# schematic.net
KiCad netlist of a schematic drawn in Altium Designer
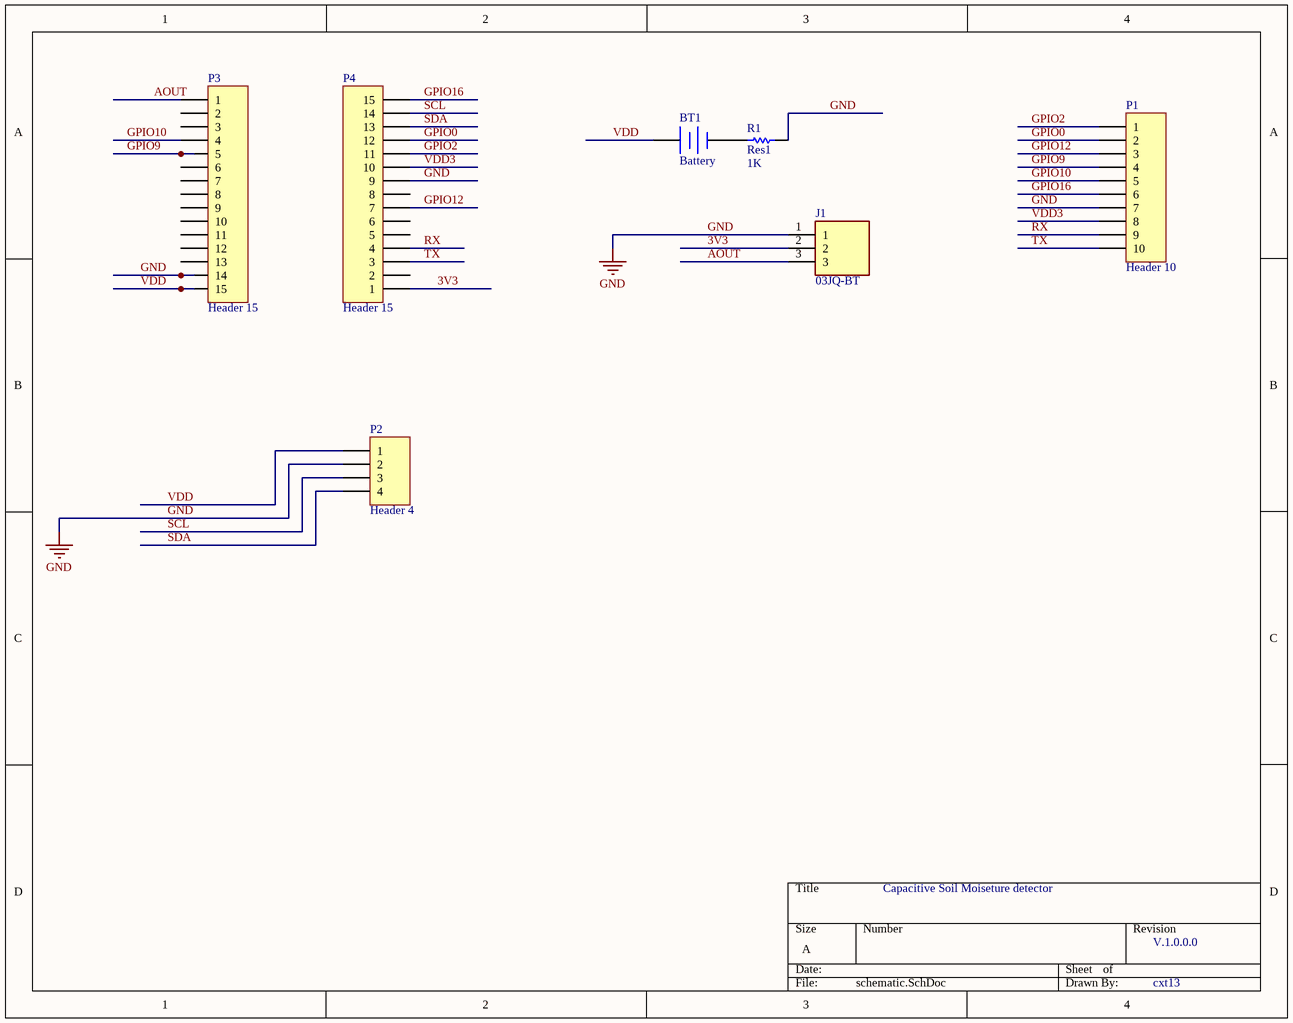
[diagram p0: schematic.SchDoc]

(export (version "E")
  (design (tool "Eeschema 10.0.6"))
  (components
    (comp (ref "BT1")
      (value "Battery")
      (footprint "BAT-2")
      (description "Multicell Battery")
      (fields (field (name "PUBLISHER") "Altium Limited"))
      (libsource (lib "Miscellaneous Devices") (part "Battery"))
    )
    (comp (ref "J1")
      (value "03JQ-BT")
      (footprint "SamacSys:SHDR3W80P0X250_1X3_1000X600X950P")
      (description "Connector")
      (libsource (lib "*") (part "03JQ-BT"))
    )
    (comp (ref "P1")
      (value "Header 10")
      (footprint "HDR1X10")
      (description "Header, 10-Pin")
      (fields (field (name "PUBLISHER") "Altium Limited"))
      (libsource (lib "Miscellaneous Connectors") (part "Header 10"))
    )
    (comp (ref "P2")
      (value "Header 4")
      (footprint "HDR1X4")
      (description "Header, 4-Pin")
      (fields (field (name "PUBLISHER") "Altium Limited"))
      (libsource (lib "Miscellaneous Connectors") (part "Header 4"))
    )
    (comp (ref "P3")
      (value "Header 15")
      (footprint "HDR1X15")
      (description "Header, 15-Pin")
      (fields (field (name "PUBLISHER") "Altium Limited"))
      (libsource (lib "") (part "Header 15_1"))
    )
    (comp (ref "P4")
      (value "Header 15")
      (footprint "HDR1X15")
      (description "Header, 15-Pin")
      (fields (field (name "PUBLISHER") "Altium Limited"))
      (libsource (lib "Miscellaneous Connectors") (part "Header 15"))
    )
    (comp (ref "R1")
      (value "Res1")
      (footprint "AXIAL-0.3")
      (description "Resistor")
      (fields (field (name "ALTIUM_VALUE") "1K") (field (name "PUBLISHER") "Altium Limited"))
      (libsource (lib "Miscellaneous Devices") (part "Res1"))
    )
  )
  (nets
    (net (code "1") (name "/3V3") (class "Default")
      (node (ref "J1") (pin "2") (pinfunction "2_2") (pintype "passive"))
      (node (ref "P4") (pin "1") (pinfunction "1_1") (pintype "passive"))
    )
    (net (code "2") (name "/AOUT") (class "Default")
      (node (ref "J1") (pin "3") (pinfunction "3_3") (pintype "passive"))
      (node (ref "P3") (pin "1") (pinfunction "1_1") (pintype "passive"))
    )
    (net (code "3") (name "/GPIO0") (class "Default")
      (node (ref "P1") (pin "2") (pinfunction "2_2") (pintype "passive"))
      (node (ref "P4") (pin "12") (pinfunction "12_12") (pintype "passive"))
    )
    (net (code "4") (name "/GPIO2") (class "Default")
      (node (ref "P1") (pin "1") (pinfunction "1_1") (pintype "passive"))
      (node (ref "P4") (pin "11") (pinfunction "11_11") (pintype "passive"))
    )
    (net (code "5") (name "/GPIO9") (class "Default")
      (node (ref "P1") (pin "4") (pinfunction "4_4") (pintype "passive"))
      (node (ref "P3") (pin "5") (pinfunction "5_5") (pintype "passive"))
    )
    (net (code "6") (name "/GPIO10") (class "Default")
      (node (ref "P1") (pin "5") (pinfunction "5_5") (pintype "passive"))
      (node (ref "P3") (pin "4") (pinfunction "4_4") (pintype "passive"))
    )
    (net (code "7") (name "/GPIO12") (class "Default")
      (node (ref "P1") (pin "3") (pinfunction "3_3") (pintype "passive"))
      (node (ref "P4") (pin "7") (pinfunction "7_7") (pintype "passive"))
    )
    (net (code "8") (name "/GPIO16") (class "Default")
      (node (ref "P1") (pin "6") (pinfunction "6_6") (pintype "passive"))
      (node (ref "P4") (pin "15") (pinfunction "15_15") (pintype "passive"))
    )
    (net (code "9") (name "/RX") (class "Default")
      (node (ref "P1") (pin "9") (pinfunction "9_9") (pintype "passive"))
      (node (ref "P4") (pin "4") (pinfunction "4_4") (pintype "passive"))
    )
    (net (code "10") (name "/SCL") (class "Default")
      (node (ref "P2") (pin "3") (pinfunction "3_3") (pintype "passive"))
      (node (ref "P4") (pin "14") (pinfunction "14_14") (pintype "passive"))
    )
    (net (code "11") (name "/SDA") (class "Default")
      (node (ref "P2") (pin "4") (pinfunction "4_4") (pintype "passive"))
      (node (ref "P4") (pin "13") (pinfunction "13_13") (pintype "passive"))
    )
    (net (code "12") (name "/TX") (class "Default")
      (node (ref "P1") (pin "10") (pinfunction "10_10") (pintype "passive"))
      (node (ref "P4") (pin "3") (pinfunction "3_3") (pintype "passive"))
    )
    (net (code "13") (name "/VDD") (class "Default")
      (node (ref "BT1") (pin "1") (pinfunction "+_1") (pintype "passive"))
      (node (ref "P2") (pin "1") (pinfunction "1_1") (pintype "passive"))
      (node (ref "P3") (pin "15") (pinfunction "15_15") (pintype "passive"))
    )
    (net (code "14") (name "/VDD3") (class "Default")
      (node (ref "P1") (pin "8") (pinfunction "8_8") (pintype "passive"))
      (node (ref "P4") (pin "10") (pinfunction "10_10") (pintype "passive"))
    )
    (net (code "15") (name "GND") (class "Default")
      (node (ref "J1") (pin "1") (pinfunction "1_1") (pintype "passive"))
      (node (ref "P1") (pin "7") (pinfunction "7_7") (pintype "passive"))
      (node (ref "P2") (pin "2") (pinfunction "2_2") (pintype "passive"))
      (node (ref "P3") (pin "14") (pinfunction "14_14") (pintype "passive"))
      (node (ref "P4") (pin "9") (pinfunction "9_9") (pintype "passive"))
      (node (ref "R1") (pin "2") (pinfunction "2_2") (pintype "passive"))
    )
    (net (code "16") (name "Net-(BT1--)") (class "Default")
      (node (ref "BT1") (pin "2") (pinfunction "-_2") (pintype "passive"))
      (node (ref "R1") (pin "1") (pinfunction "1_1") (pintype "passive"))
    )
    (net (code "17") (name "unconnected-(P3-Pad2)") (class "Default")
      (node (ref "P3") (pin "2") (pinfunction "2_2") (pintype "passive"))
    )
    (net (code "18") (name "unconnected-(P3-Pad3)") (class "Default")
      (node (ref "P3") (pin "3") (pinfunction "3_3") (pintype "passive"))
    )
    (net (code "19") (name "unconnected-(P3-Pad6)") (class "Default")
      (node (ref "P3") (pin "6") (pinfunction "6_6") (pintype "passive"))
    )
    (net (code "20") (name "unconnected-(P3-Pad7)") (class "Default")
      (node (ref "P3") (pin "7") (pinfunction "7_7") (pintype "passive"))
    )
    (net (code "21") (name "unconnected-(P3-Pad8)") (class "Default")
      (node (ref "P3") (pin "8") (pinfunction "8_8") (pintype "passive"))
    )
    (net (code "22") (name "unconnected-(P3-Pad9)") (class "Default")
      (node (ref "P3") (pin "9") (pinfunction "9_9") (pintype "passive"))
    )
    (net (code "23") (name "unconnected-(P3-Pad10)") (class "Default")
      (node (ref "P3") (pin "10") (pinfunction "10_10") (pintype "passive"))
    )
    (net (code "24") (name "unconnected-(P3-Pad11)") (class "Default")
      (node (ref "P3") (pin "11") (pinfunction "11_11") (pintype "passive"))
    )
    (net (code "25") (name "unconnected-(P3-Pad12)") (class "Default")
      (node (ref "P3") (pin "12") (pinfunction "12_12") (pintype "passive"))
    )
    (net (code "26") (name "unconnected-(P3-Pad13)") (class "Default")
      (node (ref "P3") (pin "13") (pinfunction "13_13") (pintype "passive"))
    )
    (net (code "27") (name "unconnected-(P4-Pad2)") (class "Default")
      (node (ref "P4") (pin "2") (pinfunction "2_2") (pintype "passive"))
    )
    (net (code "28") (name "unconnected-(P4-Pad5)") (class "Default")
      (node (ref "P4") (pin "5") (pinfunction "5_5") (pintype "passive"))
    )
    (net (code "29") (name "unconnected-(P4-Pad6)") (class "Default")
      (node (ref "P4") (pin "6") (pinfunction "6_6") (pintype "passive"))
    )
    (net (code "30") (name "unconnected-(P4-Pad8)") (class "Default")
      (node (ref "P4") (pin "8") (pinfunction "8_8") (pintype "passive"))
    )
  )
)
